# CanTrcvCircuit.net
KiCad netlist of a schematic drawn in Altium Designer
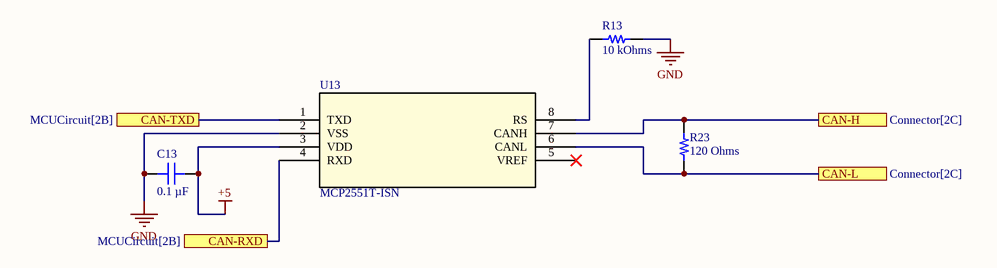
[diagram p0: CanTrcvCircuit.SchDoc]

(export (version "E")
  (design (tool "Eeschema 10.0.6"))
  (components
    (comp (ref "C13")
      (value "0.1 µF")
      (footprint "C0805")
      (description "CAP CER 0.1UF 16V X7R 0805")
      (fields
        (field (name "PART NUMBER") "0805B104K160CT")
        (field (name "MANUFACTURER") "Walsin Technology Corporation")
      )
      (libsource (lib "Celestial Altium Library - altium_library") (part "Capacitor"))
    )
    (comp (ref "R13")
      (value "10 kOhms")
      (footprint "RES 0805_2012")
      (description "RES 10 KOHM 1% 1/4W 0805")
      (fields (field (name "PART NUMBER") "AC0805FR-7W10KL") (field (name "MANUFACTURER") "Yageo"))
      (libsource (lib "Celestial Altium Library - altium_library") (part "Resistor"))
    )
    (comp (ref "R23")
      (value "120 Ohms")
      (footprint "RES 0805_2012")
      (description "RES 120 OHM 1% 1/8W 0805")
      (fields (field (name "PART NUMBER") "RC0805FR-07120RL") (field (name "MANUFACTURER") "Yageo"))
      (libsource (lib "Celestial Altium Library - altium_library") (part "Resistor"))
    )
    (comp (ref "U13")
      (value "MCP2551T-ISN")
      (footprint "MCP2551T-ISN:SOIC8-N_MC_MCH-M")
      (description "No Description Available")
      (libsource (lib "MCP2551T-ISN") (part "MCP2551T-ISN"))
    )
  )
  (nets
    (net (code "1") (name "+5") (class "Default")
      (node (ref "C13") (pin "2") (pinfunction "2_2") (pintype "passive"))
      (node (ref "U13") (pin "3") (pinfunction "VDD_3") (pintype "passive"))
    )
    (net (code "2") (name "/CAN-H") (class "Default")
      (node (ref "R23") (pin "2") (pinfunction "2_2") (pintype "passive"))
      (node (ref "U13") (pin "7") (pinfunction "CANH_7") (pintype "passive"))
    )
    (net (code "3") (name "/CAN-L") (class "Default")
      (node (ref "R23") (pin "1") (pinfunction "1_1") (pintype "passive"))
      (node (ref "U13") (pin "6") (pinfunction "CANL_6") (pintype "passive"))
    )
    (net (code "4") (name "/CAN-RXD") (class "Default")
      (node (ref "U13") (pin "4") (pinfunction "RXD_4") (pintype "passive"))
    )
    (net (code "5") (name "/CAN-TXD") (class "Default")
      (node (ref "U13") (pin "1") (pinfunction "TXD_1") (pintype "passive"))
    )
    (net (code "6") (name "GND") (class "Default")
      (node (ref "C13") (pin "1") (pinfunction "1_1") (pintype "passive"))
      (node (ref "R13") (pin "2") (pinfunction "2_2") (pintype "passive"))
      (node (ref "U13") (pin "2") (pinfunction "VSS_2") (pintype "passive"))
    )
    (net (code "7") (name "Net-(U13-RS)") (class "Default")
      (node (ref "R13") (pin "1") (pinfunction "1_1") (pintype "passive"))
      (node (ref "U13") (pin "8") (pinfunction "RS_8") (pintype "passive"))
    )
    (net (code "8") (name "unconnected-(U13-VREF-Pad5)") (class "Default")
      (node (ref "U13") (pin "5") (pinfunction "VREF_5") (pintype "passive+no_connect"))
    )
  )
)
